# untitled.net
KiCad netlist of a schematic drawn in EAGLE
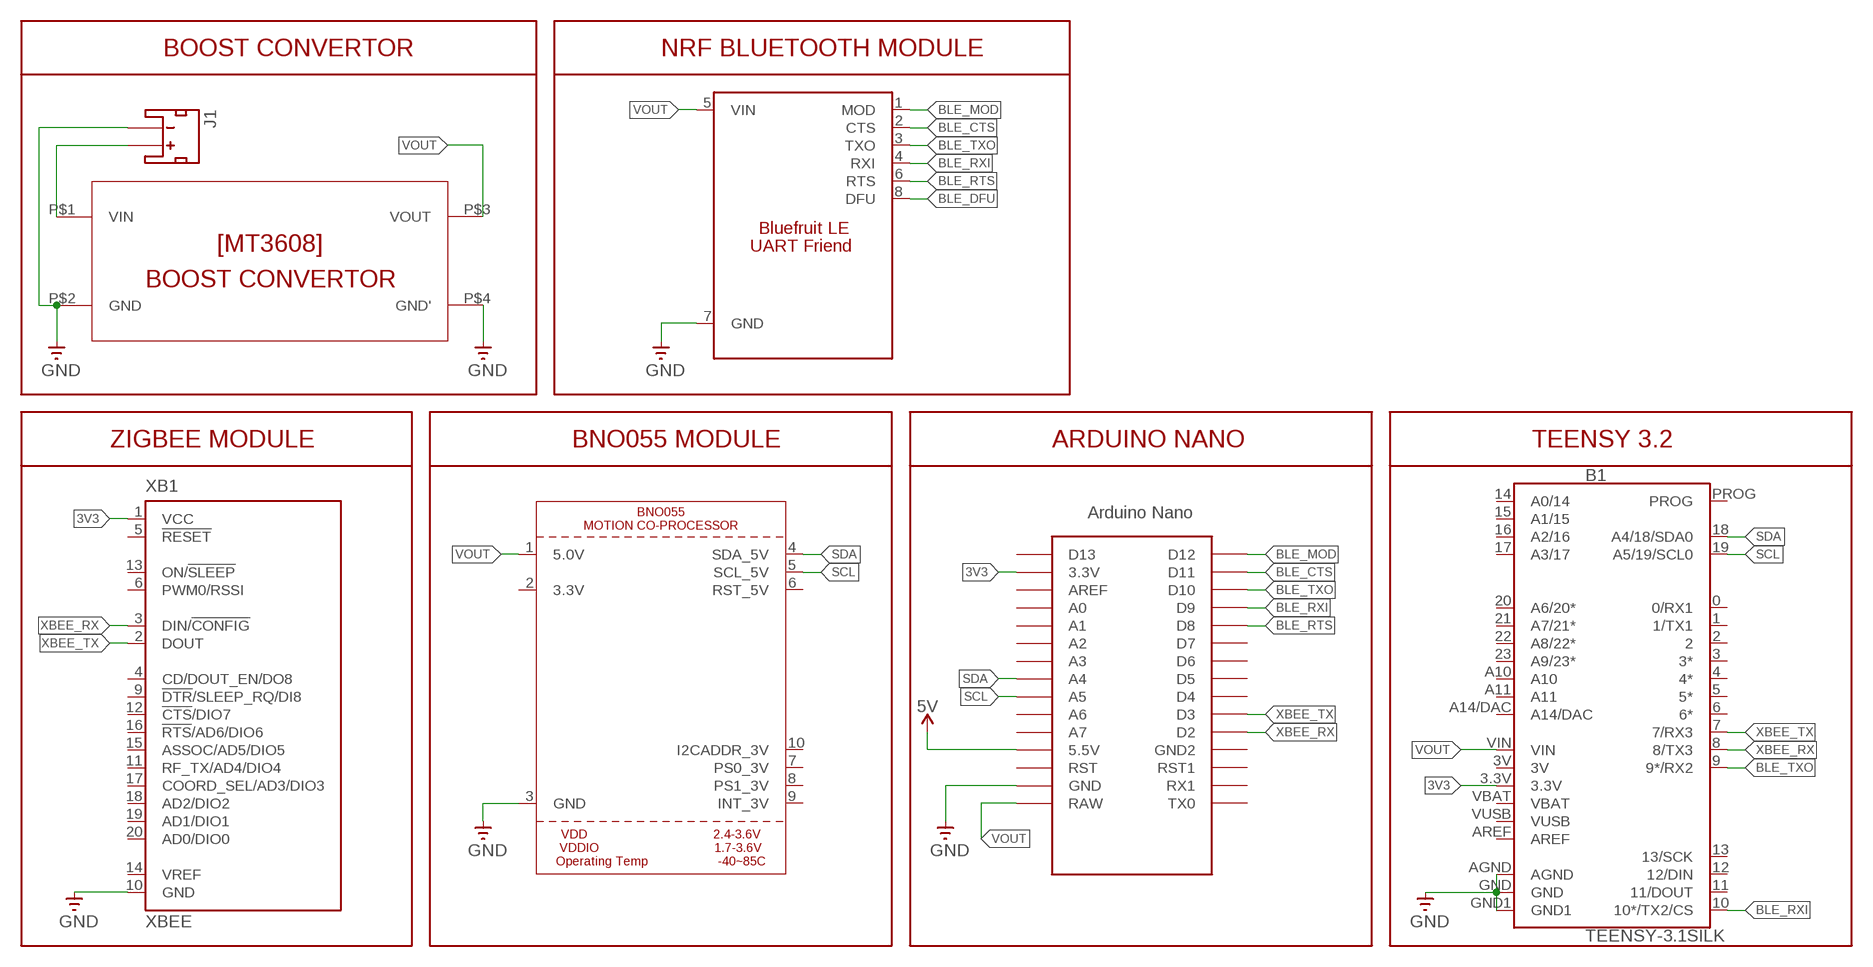
[diagram p0: schematic, sheet 1]

(export (version "E")
  (design (tool "Eeschema 10.0.6"))
  (components
    (comp (ref "B1")
      (value "TEENSY-3.1SILK")
      (footprint "eagle-import:TEENSY-3.1")
      (libsource (lib "eagle-import") (part "TEENSY-3.1SILK"))
    )
    (comp (ref "J1")
      (value "JST_2MM_MALE")
      (footprint "eagle-import:JST-2-SMD")
      (libsource (lib "eagle-import") (part "JST_2MM_MALE"))
    )
    (comp (ref "U$1")
      (value "NANO")
      (footprint "eagle-import:NANO")
      (libsource (lib "eagle-import") (part "NANO"))
    )
    (comp (ref "U$2")
      (value "BNO055")
      (footprint "eagle-import:BNO")
      (libsource (lib "eagle-import") (part "BNO055"))
    )
    (comp (ref "U$3")
      (value "MT3608")
      (footprint "eagle-import:MT3608")
      (libsource (lib "eagle-import") (part "MT3608"))
    )
    (comp (ref "U$4")
      (value "BLUEFRUIT_LE")
      (footprint "eagle-import:BLUETOOTH_FRIEND")
      (libsource (lib "eagle-import") (part "BLUEFRUIT_LE"))
    )
    (comp (ref "XB1")
      (value "XBEE")
      (footprint "eagle-import:XBEE")
      (libsource (lib "eagle-import") (part "XBEE"))
    )
  )
  (nets
    (net (code "1") (name "/3V") (class "Default")
      (node (ref "B1") (pin "3V") (pinfunction "3V_3V") (pintype "power_in"))
    )
    (net (code "2") (name "/VBAT") (class "Default")
      (node (ref "B1") (pin "VBAT") (pinfunction "VBAT_VBAT") (pintype "power_in"))
    )
    (net (code "3") (name "/VUSB") (class "Default")
      (node (ref "B1") (pin "VUSB") (pinfunction "VUSB_VUSB") (pintype "power_in"))
    )
    (net (code "4") (name "3V3") (class "Default")
      (node (ref "B1") (pin "3.3V") (pinfunction "3.3V_3.3V") (pintype "power_in"))
      (node (ref "U$1") (pin "3.3V") (pinfunction "3.3V_3.3V") (pintype "bidirectional"))
      (node (ref "XB1") (pin "1") (pinfunction "VCC_1") (pintype "power_in"))
    )
    (net (code "5") (name "5V") (class "Default")
      (node (ref "U$1") (pin "5V") (pinfunction "5.5V_5V") (pintype "bidirectional"))
    )
    (net (code "6") (name "BLE_CTS") (class "Default")
      (node (ref "U$1") (pin "D11") (pinfunction "D11_D11") (pintype "bidirectional"))
      (node (ref "U$4") (pin "2") (pinfunction "CTS_2") (pintype "bidirectional"))
    )
    (net (code "7") (name "BLE_DFU") (class "Default")
      (node (ref "U$4") (pin "8") (pinfunction "DFU_8") (pintype "bidirectional"))
    )
    (net (code "8") (name "BLE_MOD") (class "Default")
      (node (ref "U$1") (pin "D12") (pinfunction "D12_D12") (pintype "bidirectional"))
      (node (ref "U$4") (pin "1") (pinfunction "MOD_1") (pintype "bidirectional"))
    )
    (net (code "9") (name "BLE_RTS") (class "Default")
      (node (ref "U$1") (pin "D8") (pinfunction "D8_D8") (pintype "bidirectional"))
      (node (ref "U$4") (pin "6") (pinfunction "RTS_6") (pintype "bidirectional"))
    )
    (net (code "10") (name "BLE_RXI") (class "Default")
      (node (ref "B1") (pin "10") (pinfunction "10*/TX2/CS_10") (pintype "bidirectional"))
      (node (ref "U$1") (pin "D9") (pinfunction "D9_D9") (pintype "bidirectional"))
      (node (ref "U$4") (pin "4") (pinfunction "RXI_4") (pintype "bidirectional"))
    )
    (net (code "11") (name "BLE_TXO") (class "Default")
      (node (ref "B1") (pin "9") (pinfunction "9*/RX2_9") (pintype "bidirectional"))
      (node (ref "U$1") (pin "D10") (pinfunction "D10_D10") (pintype "bidirectional"))
      (node (ref "U$4") (pin "3") (pinfunction "TXO_3") (pintype "bidirectional"))
    )
    (net (code "12") (name "GND") (class "Default")
      (node (ref "B1") (pin "AGND") (pinfunction "AGND_AGND") (pintype "power_in"))
      (node (ref "B1") (pin "GND") (pinfunction "GND_GND") (pintype "power_in"))
      (node (ref "B1") (pin "GND1") (pinfunction "GND1_GND1") (pintype "power_in"))
      (node (ref "J1") (pin "1") (pinfunction "-_1") (pintype "bidirectional"))
      (node (ref "U$1") (pin "GND") (pinfunction "GND_GND") (pintype "bidirectional"))
      (node (ref "U$2") (pin "3") (pinfunction "GND_3") (pintype "bidirectional"))
      (node (ref "U$3") (pin "P$2") (pinfunction "GND_P$2") (pintype "bidirectional"))
      (node (ref "U$3") (pin "P$4") (pinfunction "GND'_P$4") (pintype "bidirectional"))
      (node (ref "U$4") (pin "7") (pinfunction "GND_7") (pintype "bidirectional"))
      (node (ref "XB1") (pin "10") (pinfunction "GND_10") (pintype "power_in"))
    )
    (net (code "13") (name "Net-(J1-+)") (class "Default")
      (node (ref "J1") (pin "2") (pinfunction "+_2") (pintype "bidirectional"))
      (node (ref "U$3") (pin "P$1") (pinfunction "VIN_P$1") (pintype "bidirectional"))
    )
    (net (code "14") (name "SCL") (class "Default")
      (node (ref "B1") (pin "19") (pinfunction "A5/19/SCL0_19") (pintype "bidirectional"))
      (node (ref "U$1") (pin "A5") (pinfunction "A5_A5") (pintype "bidirectional"))
      (node (ref "U$2") (pin "5") (pinfunction "SCL_5V_5") (pintype "bidirectional"))
    )
    (net (code "15") (name "SDA") (class "Default")
      (node (ref "B1") (pin "18") (pinfunction "A4/18/SDA0_18") (pintype "bidirectional"))
      (node (ref "U$1") (pin "A4") (pinfunction "A4_A4") (pintype "bidirectional"))
      (node (ref "U$2") (pin "4") (pinfunction "SDA_5V_4") (pintype "bidirectional"))
    )
    (net (code "16") (name "VOUT") (class "Default")
      (node (ref "B1") (pin "VIN") (pinfunction "VIN_VIN") (pintype "power_in"))
      (node (ref "U$1") (pin "RAW") (pinfunction "RAW_RAW") (pintype "bidirectional"))
      (node (ref "U$2") (pin "1") (pinfunction "5.0V_1") (pintype "bidirectional"))
      (node (ref "U$3") (pin "P$3") (pinfunction "VOUT_P$3") (pintype "bidirectional"))
      (node (ref "U$4") (pin "5") (pinfunction "VIN_5") (pintype "bidirectional"))
    )
    (net (code "17") (name "XBEE_RX") (class "Default")
      (node (ref "B1") (pin "8") (pinfunction "8/TX3_8") (pintype "bidirectional"))
      (node (ref "U$1") (pin "D2") (pinfunction "D2_D2") (pintype "bidirectional"))
      (node (ref "XB1") (pin "3") (pinfunction "DIN/~{CONFIG}_3") (pintype "input"))
    )
    (net (code "18") (name "XBEE_TX") (class "Default")
      (node (ref "B1") (pin "7") (pinfunction "7/RX3_7") (pintype "bidirectional"))
      (node (ref "U$1") (pin "D3") (pinfunction "D3_D3") (pintype "bidirectional"))
      (node (ref "XB1") (pin "2") (pinfunction "DOUT_2") (pintype "output"))
    )
    (net (code "19") (name "unconnected-(B1-0{slash}RX1-Pad0)") (class "Default")
      (node (ref "B1") (pin "0") (pinfunction "0/RX1_0") (pintype "bidirectional"))
    )
    (net (code "20") (name "unconnected-(B1-1{slash}TX1-Pad1)") (class "Default")
      (node (ref "B1") (pin "1") (pinfunction "1/TX1_1") (pintype "bidirectional"))
    )
    (net (code "21") (name "unconnected-(B1-3*-Pad3)") (class "Default")
      (node (ref "B1") (pin "3") (pinfunction "3*_3") (pintype "bidirectional"))
    )
    (net (code "22") (name "unconnected-(B1-4*-Pad4)") (class "Default")
      (node (ref "B1") (pin "4") (pinfunction "4*_4") (pintype "bidirectional"))
    )
    (net (code "23") (name "unconnected-(B1-5*-Pad5)") (class "Default")
      (node (ref "B1") (pin "5") (pinfunction "5*_5") (pintype "bidirectional"))
    )
    (net (code "24") (name "unconnected-(B1-6*-Pad6)") (class "Default")
      (node (ref "B1") (pin "6") (pinfunction "6*_6") (pintype "bidirectional"))
    )
    (net (code "25") (name "unconnected-(B1-11{slash}DOUT-Pad11)") (class "Default")
      (node (ref "B1") (pin "11") (pinfunction "11/DOUT_11") (pintype "bidirectional"))
    )
    (net (code "26") (name "unconnected-(B1-12{slash}DIN-Pad12)") (class "Default")
      (node (ref "B1") (pin "12") (pinfunction "12/DIN_12") (pintype "bidirectional"))
    )
    (net (code "27") (name "unconnected-(B1-13{slash}SCK-Pad13)") (class "Default")
      (node (ref "B1") (pin "13") (pinfunction "13/SCK_13") (pintype "bidirectional"))
    )
    (net (code "28") (name "unconnected-(B1-A0{slash}14-Pad14)") (class "Default")
      (node (ref "B1") (pin "14") (pinfunction "A0/14_14") (pintype "bidirectional"))
    )
    (net (code "29") (name "unconnected-(B1-A1{slash}15-Pad15)") (class "Default")
      (node (ref "B1") (pin "15") (pinfunction "A1/15_15") (pintype "bidirectional"))
    )
    (net (code "30") (name "unconnected-(B1-A2{slash}16-Pad16)") (class "Default")
      (node (ref "B1") (pin "16") (pinfunction "A2/16_16") (pintype "bidirectional"))
    )
    (net (code "31") (name "unconnected-(B1-A3{slash}17-Pad17)") (class "Default")
      (node (ref "B1") (pin "17") (pinfunction "A3/17_17") (pintype "bidirectional"))
    )
    (net (code "32") (name "unconnected-(B1-A6{slash}20*-Pad20)") (class "Default")
      (node (ref "B1") (pin "20") (pinfunction "A6/20*_20") (pintype "bidirectional"))
    )
    (net (code "33") (name "unconnected-(B1-A7{slash}21*-Pad21)") (class "Default")
      (node (ref "B1") (pin "21") (pinfunction "A7/21*_21") (pintype "bidirectional"))
    )
    (net (code "34") (name "unconnected-(B1-A8{slash}22*-Pad22)") (class "Default")
      (node (ref "B1") (pin "22") (pinfunction "A8/22*_22") (pintype "bidirectional"))
    )
    (net (code "35") (name "unconnected-(B1-A9{slash}23*-Pad23)") (class "Default")
      (node (ref "B1") (pin "23") (pinfunction "A9/23*_23") (pintype "bidirectional"))
    )
    (net (code "36") (name "unconnected-(B1-Pad2)") (class "Default")
      (node (ref "B1") (pin "2") (pinfunction "2_2") (pintype "bidirectional"))
    )
    (net (code "37") (name "unconnected-(B1-PadA10)") (class "Default")
      (node (ref "B1") (pin "A10") (pinfunction "A10_A10") (pintype "bidirectional"))
    )
    (net (code "38") (name "unconnected-(B1-PadA11)") (class "Default")
      (node (ref "B1") (pin "A11") (pinfunction "A11_A11") (pintype "bidirectional"))
    )
    (net (code "39") (name "unconnected-(B1-PadA14{slash}DAC)") (class "Default")
      (node (ref "B1") (pin "A14/DAC") (pinfunction "A14/DAC_A14/DAC") (pintype "bidirectional"))
    )
    (net (code "40") (name "unconnected-(B1-PadAREF)") (class "Default")
      (node (ref "B1") (pin "AREF") (pinfunction "AREF_AREF") (pintype "bidirectional"))
    )
    (net (code "41") (name "unconnected-(B1-PadPROG)") (class "Default")
      (node (ref "B1") (pin "PROG") (pinfunction "PROG_PROG") (pintype "bidirectional"))
    )
    (net (code "42") (name "unconnected-(J1-PAD1-PadNC1)") (class "Default")
      (node (ref "J1") (pin "NC1") (pinfunction "PAD1_NC1") (pintype "bidirectional"))
    )
    (net (code "43") (name "unconnected-(J1-PAD2-PadNC2)") (class "Default")
      (node (ref "J1") (pin "NC2") (pinfunction "PAD2_NC2") (pintype "bidirectional"))
    )
    (net (code "44") (name "unconnected-(U$1-GND2-PadGND1)") (class "Default")
      (node (ref "U$1") (pin "GND1") (pinfunction "GND2_GND1") (pintype "bidirectional"))
    )
    (net (code "45") (name "unconnected-(U$1-PadA0)") (class "Default")
      (node (ref "U$1") (pin "A0") (pinfunction "A0_A0") (pintype "bidirectional"))
    )
    (net (code "46") (name "unconnected-(U$1-PadA1)") (class "Default")
      (node (ref "U$1") (pin "A1") (pinfunction "A1_A1") (pintype "bidirectional"))
    )
    (net (code "47") (name "unconnected-(U$1-PadA2)") (class "Default")
      (node (ref "U$1") (pin "A2") (pinfunction "A2_A2") (pintype "bidirectional"))
    )
    (net (code "48") (name "unconnected-(U$1-PadA3)") (class "Default")
      (node (ref "U$1") (pin "A3") (pinfunction "A3_A3") (pintype "bidirectional"))
    )
    (net (code "49") (name "unconnected-(U$1-PadA6)") (class "Default")
      (node (ref "U$1") (pin "A6") (pinfunction "A6_A6") (pintype "bidirectional"))
    )
    (net (code "50") (name "unconnected-(U$1-PadA7)") (class "Default")
      (node (ref "U$1") (pin "A7") (pinfunction "A7_A7") (pintype "bidirectional"))
    )
    (net (code "51") (name "unconnected-(U$1-PadAREF)") (class "Default")
      (node (ref "U$1") (pin "AREF") (pinfunction "AREF_AREF") (pintype "bidirectional"))
    )
    (net (code "52") (name "unconnected-(U$1-PadD4)") (class "Default")
      (node (ref "U$1") (pin "D4") (pinfunction "D4_D4") (pintype "bidirectional"))
    )
    (net (code "53") (name "unconnected-(U$1-PadD5)") (class "Default")
      (node (ref "U$1") (pin "D5") (pinfunction "D5_D5") (pintype "bidirectional"))
    )
    (net (code "54") (name "unconnected-(U$1-PadD6)") (class "Default")
      (node (ref "U$1") (pin "D6") (pinfunction "D6_D6") (pintype "bidirectional"))
    )
    (net (code "55") (name "unconnected-(U$1-PadD7)") (class "Default")
      (node (ref "U$1") (pin "D7") (pinfunction "D7_D7") (pintype "bidirectional"))
    )
    (net (code "56") (name "unconnected-(U$1-PadD13)") (class "Default")
      (node (ref "U$1") (pin "D13") (pinfunction "D13_D13") (pintype "bidirectional"))
    )
    (net (code "57") (name "unconnected-(U$1-PadICSP1)") (class "Default")
      (node (ref "U$1") (pin "ICSP1") (pinfunction "ICSP1_ICSP1") (pintype "bidirectional"))
    )
    (net (code "58") (name "unconnected-(U$1-PadICSP2)") (class "Default")
      (node (ref "U$1") (pin "ICSP2") (pinfunction "ICSP2_ICSP2") (pintype "bidirectional"))
    )
    (net (code "59") (name "unconnected-(U$1-PadICSP3)") (class "Default")
      (node (ref "U$1") (pin "ICSP3") (pinfunction "ICSP3_ICSP3") (pintype "bidirectional"))
    )
    (net (code "60") (name "unconnected-(U$1-PadICSP4)") (class "Default")
      (node (ref "U$1") (pin "ICSP4") (pinfunction "ICSP4_ICSP4") (pintype "bidirectional"))
    )
    (net (code "61") (name "unconnected-(U$1-PadICSP5)") (class "Default")
      (node (ref "U$1") (pin "ICSP5") (pinfunction "ICSP5_ICSP5") (pintype "bidirectional"))
    )
    (net (code "62") (name "unconnected-(U$1-PadICSP6)") (class "Default")
      (node (ref "U$1") (pin "ICSP6") (pinfunction "ICSP6_ICSP6") (pintype "bidirectional"))
    )
    (net (code "63") (name "unconnected-(U$1-PadRST)") (class "Default")
      (node (ref "U$1") (pin "RST") (pinfunction "RST_RST") (pintype "bidirectional"))
    )
    (net (code "64") (name "unconnected-(U$1-PadRST1)") (class "Default")
      (node (ref "U$1") (pin "RST1") (pinfunction "RST1_RST1") (pintype "bidirectional"))
    )
    (net (code "65") (name "unconnected-(U$1-PadRX1)") (class "Default")
      (node (ref "U$1") (pin "RX1") (pinfunction "RX1_RX1") (pintype "bidirectional"))
    )
    (net (code "66") (name "unconnected-(U$1-PadTX0)") (class "Default")
      (node (ref "U$1") (pin "TX0") (pinfunction "TX0_TX0") (pintype "bidirectional"))
    )
    (net (code "67") (name "unconnected-(U$2-3.3V-Pad2)") (class "Default")
      (node (ref "U$2") (pin "2") (pinfunction "3.3V_2") (pintype "bidirectional"))
    )
    (net (code "68") (name "unconnected-(U$2-I2CADDR_3V-Pad10)") (class "Default")
      (node (ref "U$2") (pin "10") (pinfunction "I2CADDR_3V_10") (pintype "bidirectional"))
    )
    (net (code "69") (name "unconnected-(U$2-INT_3V-Pad9)") (class "Default")
      (node (ref "U$2") (pin "9") (pinfunction "INT_3V_9") (pintype "bidirectional"))
    )
    (net (code "70") (name "unconnected-(U$2-PS0_3V-Pad7)") (class "Default")
      (node (ref "U$2") (pin "7") (pinfunction "PS0_3V_7") (pintype "bidirectional"))
    )
    (net (code "71") (name "unconnected-(U$2-PS1_3V-Pad8)") (class "Default")
      (node (ref "U$2") (pin "8") (pinfunction "PS1_3V_8") (pintype "bidirectional"))
    )
    (net (code "72") (name "unconnected-(U$2-RST_5V-Pad6)") (class "Default")
      (node (ref "U$2") (pin "6") (pinfunction "RST_5V_6") (pintype "bidirectional"))
    )
    (net (code "73") (name "unconnected-(XB1-AD0{slash}DIO0-Pad20)") (class "Default")
      (node (ref "XB1") (pin "20") (pinfunction "AD0/DIO0_20") (pintype "bidirectional"))
    )
    (net (code "74") (name "unconnected-(XB1-AD1{slash}DIO1-Pad19)") (class "Default")
      (node (ref "XB1") (pin "19") (pinfunction "AD1/DIO1_19") (pintype "bidirectional"))
    )
    (net (code "75") (name "unconnected-(XB1-AD2{slash}DIO2-Pad18)") (class "Default")
      (node (ref "XB1") (pin "18") (pinfunction "AD2/DIO2_18") (pintype "bidirectional"))
    )
    (net (code "76") (name "unconnected-(XB1-ASSOC{slash}AD5{slash}DIO5-Pad15)") (class "Default")
      (node (ref "XB1") (pin "15") (pinfunction "ASSOC/AD5/DIO5_15") (pintype "bidirectional"))
    )
    (net (code "77") (name "unconnected-(XB1-CD{slash}DOUT_EN{slash}DO8-Pad4)") (class "Default")
      (node (ref "XB1") (pin "4") (pinfunction "CD/DOUT_EN/DO8_4") (pintype "output"))
    )
    (net (code "78") (name "unconnected-(XB1-COORD_SEL{slash}AD3{slash}DIO3-Pad17)") (class "Default")
      (node (ref "XB1") (pin "17") (pinfunction "COORD_SEL/AD3/DIO3_17") (pintype "bidirectional"))
    )
    (net (code "79") (name "unconnected-(XB1-ON{slash}~{SLEEP}-Pad13)") (class "Default")
      (node (ref "XB1") (pin "13") (pinfunction "ON/~{SLEEP}_13") (pintype "output"))
    )
    (net (code "80") (name "unconnected-(XB1-PWM0{slash}RSSI-Pad6)") (class "Default")
      (node (ref "XB1") (pin "6") (pinfunction "PWM0/RSSI_6") (pintype "output"))
    )
    (net (code "81") (name "unconnected-(XB1-RF_TX{slash}AD4{slash}DIO4-Pad11)") (class "Default")
      (node (ref "XB1") (pin "11") (pinfunction "RF_TX/AD4/DIO4_11") (pintype "bidirectional"))
    )
    (net (code "82") (name "unconnected-(XB1-VREF-Pad14)") (class "Default")
      (node (ref "XB1") (pin "14") (pinfunction "VREF_14") (pintype "input"))
    )
    (net (code "83") (name "unconnected-(XB1-~{CTS}{slash}DIO7-Pad12)") (class "Default")
      (node (ref "XB1") (pin "12") (pinfunction "~{CTS}/DIO7_12") (pintype "bidirectional"))
    )
    (net (code "84") (name "unconnected-(XB1-~{DTR}{slash}SLEEP_RQ{slash}DI8-Pad9)") (class "Default")
      (node (ref "XB1") (pin "9") (pinfunction "~{DTR}/SLEEP_RQ/DI8_9") (pintype "bidirectional"))
    )
    (net (code "85") (name "unconnected-(XB1-~{RESET}-Pad5)") (class "Default")
      (node (ref "XB1") (pin "5") (pinfunction "~{RESET}_5") (pintype "input"))
    )
    (net (code "86") (name "unconnected-(XB1-~{RTS}{slash}AD6{slash}DIO6-Pad16)") (class "Default")
      (node (ref "XB1") (pin "16") (pinfunction "~{RTS}/AD6/DIO6_16") (pintype "bidirectional"))
    )
  )
)
